# Power_Distribution_-_Strobe_and_Center_B.net
KiCad netlist of a schematic drawn in Altium Designer
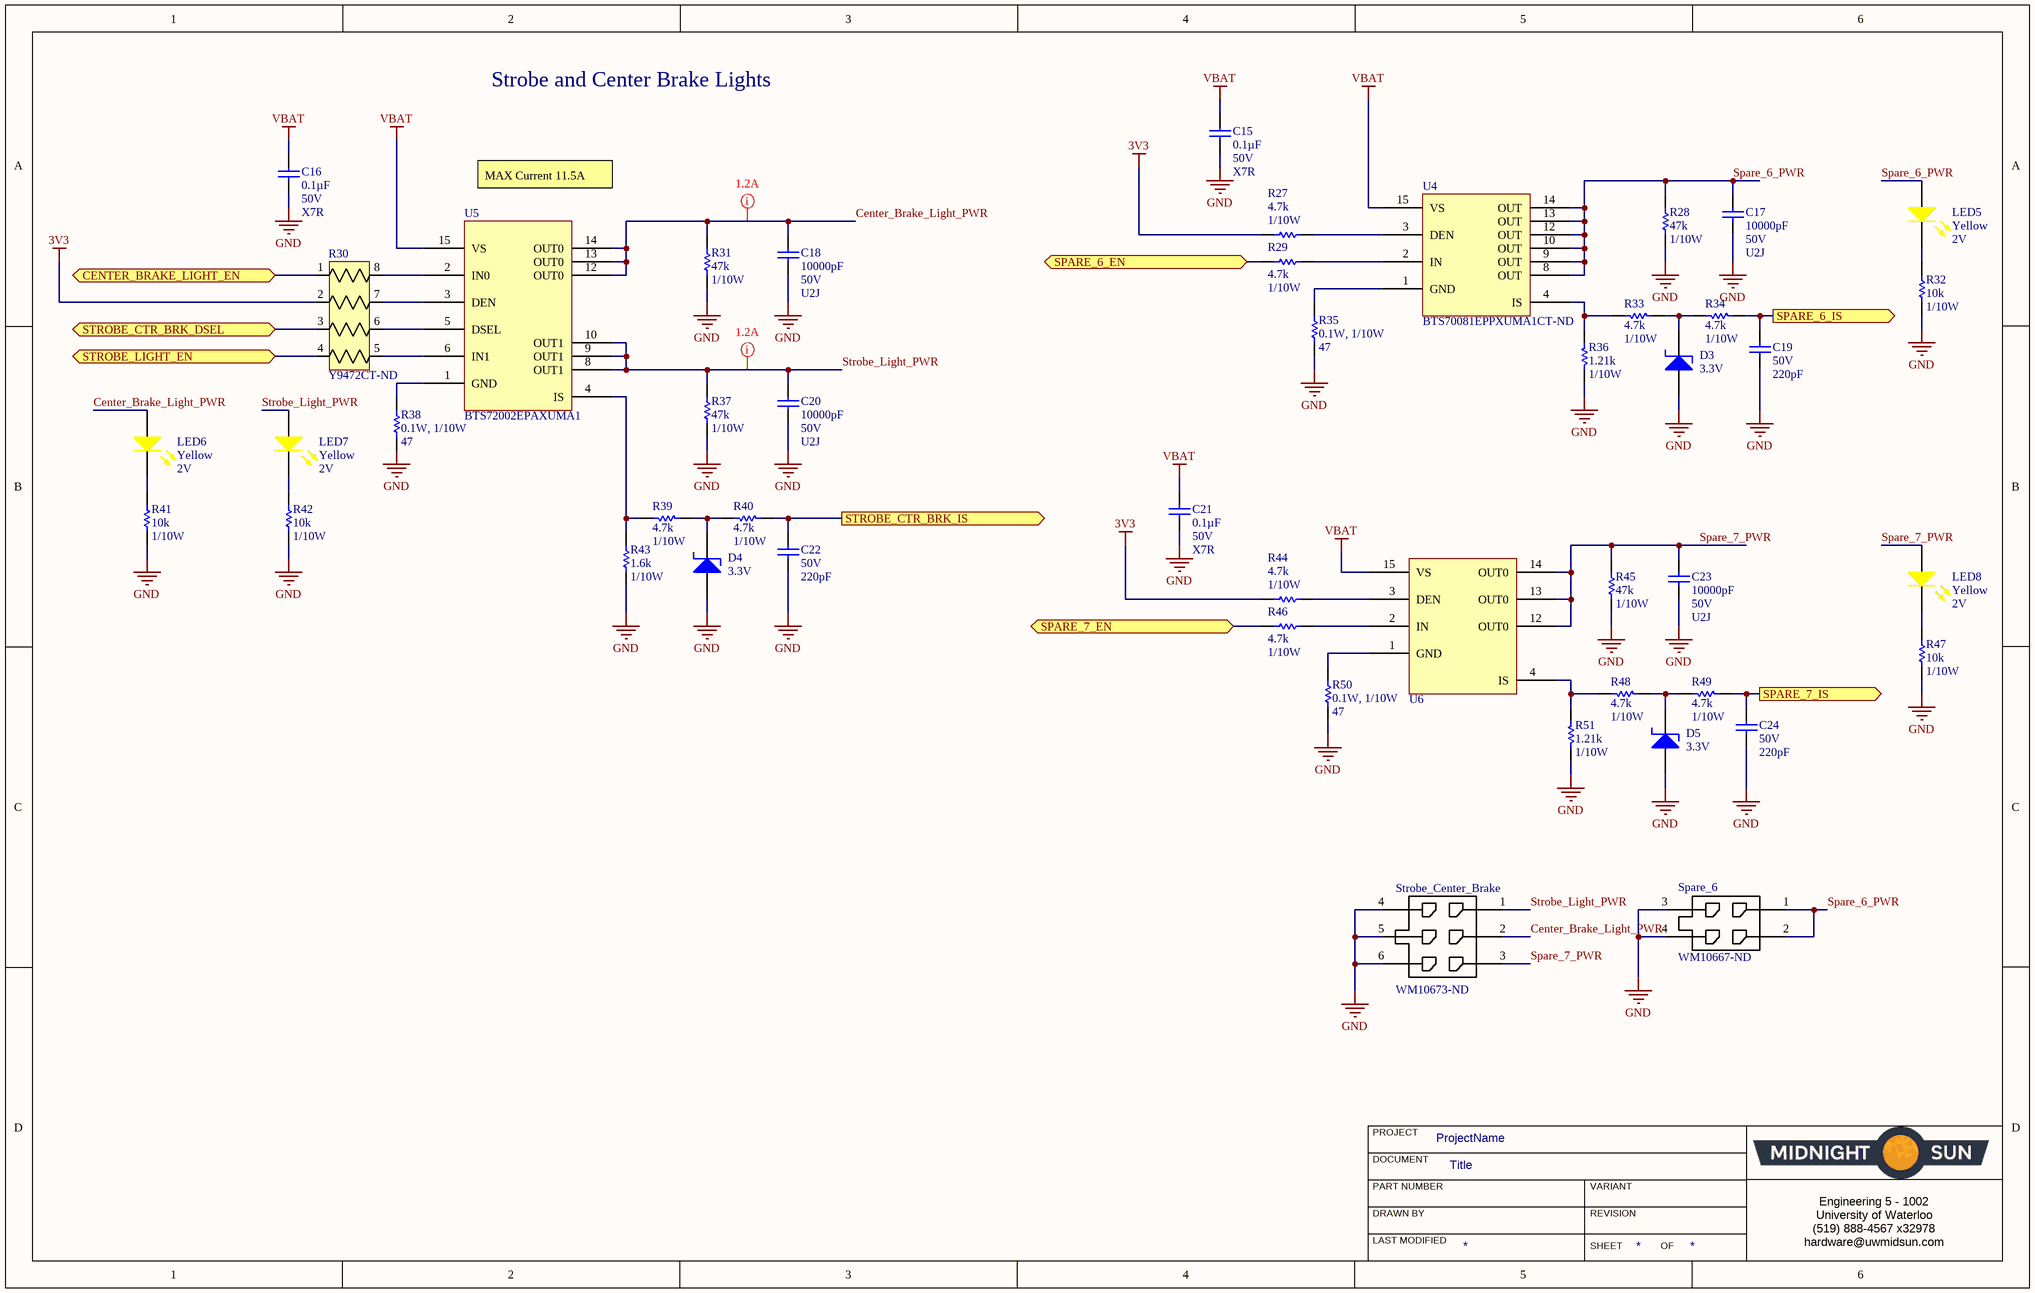
[diagram p0: Power Distribution - Strobe and Center Brake Lights.SchDoc]

(export (version "E")
  (design (tool "Eeschema 10.0.6"))
  (components
    (comp (ref "C15")
      (value "CAP CER 0.1UF 50V 10% X7R 0603")
      (footprint "CAP, 0603")
      (description "0.10µF ±10% 50V Ceramic Capacitor X7R 0603 (1608 Metric)")
      (fields
        (field (name "TOLERANCE") "±10%")
        (field (name "CAPACITANCE") "0.1µF")
        (field (name "VOLTAGE") "50V")
        (field (name "TEMPERATURE COEFFICIENT") "X7R")
      )
      (libsource (lib "Schematic Diagrams") (part "CAP CER 0.1UF 50V 10% X7R 0603"))
    )
    (comp (ref "C16")
      (value "CAP CER 0.1UF 50V 10% X7R 0603")
      (footprint "CAP, 0603")
      (description "0.10µF ±10% 50V Ceramic Capacitor X7R 0603 (1608 Metric)")
      (fields
        (field (name "TOLERANCE") "±10%")
        (field (name "CAPACITANCE") "0.1µF")
        (field (name "VOLTAGE") "50V")
        (field (name "TEMPERATURE COEFFICIENT") "X7R")
      )
      (libsource (lib "Schematic Diagrams") (part "CAP CER 0.1UF 50V 10% X7R 0603"))
    )
    (comp (ref "C17")
      (value "CAP CER 10nF 50V 5% X7R 0603")
      (footprint "CAP, 0603")
      (description "10000pF ±5% 50V Ceramic Capacitor U2J 0603 (1608 Metric)")
      (fields
        (field (name "TOLERANCE") "±5%")
        (field (name "CAPACITANCE") "10000pF")
        (field (name "VOLTAGE") "50V")
        (field (name "TEMPERATURE COEFFICIENT") "U2J")
      )
      (libsource (lib "Schematic Diagrams") (part "CAP CER 10nF 50V 5% X7R 0603"))
    )
    (comp (ref "C18")
      (value "CAP CER 10nF 50V 5% X7R 0603")
      (footprint "CAP, 0603")
      (description "10000pF ±5% 50V Ceramic Capacitor U2J 0603 (1608 Metric)")
      (fields
        (field (name "TOLERANCE") "±5%")
        (field (name "CAPACITANCE") "10000pF")
        (field (name "VOLTAGE") "50V")
        (field (name "TEMPERATURE COEFFICIENT") "U2J")
      )
      (libsource (lib "Schematic Diagrams") (part "CAP CER 10nF 50V 5% X7R 0603"))
    )
    (comp (ref "C19")
      (value "CAP CER 220PF 50V C0G/NP0 0603")
      (footprint "CAP, 0603")
      (description "220pF ±5% 50V Ceramic Capacitor C0G, NP0 0603 (1608 Metric)")
      (fields
        (field (name "MANUFACTURER") "KEMET")
        (field (name "TOLERANCE") "5%")
        (field (name "VOLTAGE RATING") "50V")
        (field (name "CAPACITANCE") "220pF")
      )
      (libsource (lib "Schematic Diagrams") (part "CAP CER 220PF 50V C0G/NP0 0603"))
    )
    (comp (ref "C20")
      (value "CAP CER 10nF 50V 5% X7R 0603")
      (footprint "CAP, 0603")
      (description "10000pF ±5% 50V Ceramic Capacitor U2J 0603 (1608 Metric)")
      (fields
        (field (name "TOLERANCE") "±5%")
        (field (name "CAPACITANCE") "10000pF")
        (field (name "VOLTAGE") "50V")
        (field (name "TEMPERATURE COEFFICIENT") "U2J")
      )
      (libsource (lib "Schematic Diagrams") (part "CAP CER 10nF 50V 5% X7R 0603"))
    )
    (comp (ref "C21")
      (value "CAP CER 0.1UF 50V 10% X7R 0603")
      (footprint "CAP, 0603")
      (description "0.10µF ±10% 50V Ceramic Capacitor X7R 0603 (1608 Metric)")
      (fields
        (field (name "TOLERANCE") "±10%")
        (field (name "CAPACITANCE") "0.1µF")
        (field (name "VOLTAGE") "50V")
        (field (name "TEMPERATURE COEFFICIENT") "X7R")
      )
      (libsource (lib "Schematic Diagrams") (part "CAP CER 0.1UF 50V 10% X7R 0603"))
    )
    (comp (ref "C22")
      (value "CAP CER 220PF 50V C0G/NP0 0603")
      (footprint "CAP, 0603")
      (description "220pF ±5% 50V Ceramic Capacitor C0G, NP0 0603 (1608 Metric)")
      (fields
        (field (name "MANUFACTURER") "KEMET")
        (field (name "TOLERANCE") "5%")
        (field (name "VOLTAGE RATING") "50V")
        (field (name "CAPACITANCE") "220pF")
      )
      (libsource (lib "Schematic Diagrams") (part "CAP CER 220PF 50V C0G/NP0 0603"))
    )
    (comp (ref "C23")
      (value "CAP CER 10nF 50V 5% X7R 0603")
      (footprint "CAP, 0603")
      (description "10000pF ±5% 50V Ceramic Capacitor U2J 0603 (1608 Metric)")
      (fields
        (field (name "TOLERANCE") "±5%")
        (field (name "CAPACITANCE") "10000pF")
        (field (name "VOLTAGE") "50V")
        (field (name "TEMPERATURE COEFFICIENT") "U2J")
      )
      (libsource (lib "Schematic Diagrams") (part "CAP CER 10nF 50V 5% X7R 0603"))
    )
    (comp (ref "C24")
      (value "CAP CER 220PF 50V C0G/NP0 0603")
      (footprint "CAP, 0603")
      (description "220pF ±5% 50V Ceramic Capacitor C0G, NP0 0603 (1608 Metric)")
      (fields
        (field (name "MANUFACTURER") "KEMET")
        (field (name "TOLERANCE") "5%")
        (field (name "VOLTAGE RATING") "50V")
        (field (name "CAPACITANCE") "220pF")
      )
      (libsource (lib "Schematic Diagrams") (part "CAP CER 220PF 50V C0G/NP0 0603"))
    )
    (comp (ref "D3")
      (value "DIODE ZENER 3.3V 200MW SOD323")
      (footprint "sod-323")
      (description "Zener Diode 3.3V 200mW ±5% Surface Mount SOD-323")
      (fields (field (name "VOLTAGE") "3.3V"))
      (libsource (lib "Schematic Diagrams") (part "DIODE ZENER 3.3V 200MW SOD323"))
    )
    (comp (ref "D4")
      (value "DIODE ZENER 3.3V 200MW SOD323")
      (footprint "sod-323")
      (description "Zener Diode 3.3V 200mW ±5% Surface Mount SOD-323")
      (fields (field (name "VOLTAGE") "3.3V"))
      (libsource (lib "Schematic Diagrams") (part "DIODE ZENER 3.3V 200MW SOD323"))
    )
    (comp (ref "D5")
      (value "DIODE ZENER 3.3V 200MW SOD323")
      (footprint "sod-323")
      (description "Zener Diode 3.3V 200mW ±5% Surface Mount SOD-323")
      (fields (field (name "VOLTAGE") "3.3V"))
      (libsource (lib "Schematic Diagrams") (part "DIODE ZENER 3.3V 200MW SOD323"))
    )
    (comp (ref "LED5")
      (value "LED YELLOW CLEAR 2.1V 0603")
      (footprint "LED_0603")
      (description "Yellow 590nm LED Indication - Discrete 2V 0603 (1608 Metric)")
      (fields
        (field (name "MANUFACTURER") "Wurth Electronics Inc.")
        (field (name "MANUFACTURER PART NUMBER") "150060YS75000")
        (field (name "COLOR") "Yellow")
        (field (name "VOLTAGE - FORWARD (VF) (TYP)") "2V")
      )
      (libsource (lib "Schematic Diagrams") (part "LED YELLOW CLEAR 2.1V 0603"))
    )
    (comp (ref "LED6")
      (value "LED YELLOW CLEAR 2.1V 0603")
      (footprint "LED_0603")
      (description "Yellow 590nm LED Indication - Discrete 2V 0603 (1608 Metric)")
      (fields
        (field (name "MANUFACTURER") "Wurth Electronics Inc.")
        (field (name "MANUFACTURER PART NUMBER") "150060YS75000")
        (field (name "COLOR") "Yellow")
        (field (name "VOLTAGE - FORWARD (VF) (TYP)") "2V")
      )
      (libsource (lib "Schematic Diagrams") (part "LED YELLOW CLEAR 2.1V 0603"))
    )
    (comp (ref "LED7")
      (value "LED YELLOW CLEAR 2.1V 0603")
      (footprint "LED_0603")
      (description "Yellow 590nm LED Indication - Discrete 2V 0603 (1608 Metric)")
      (fields
        (field (name "MANUFACTURER") "Wurth Electronics Inc.")
        (field (name "MANUFACTURER PART NUMBER") "150060YS75000")
        (field (name "COLOR") "Yellow")
        (field (name "VOLTAGE - FORWARD (VF) (TYP)") "2V")
      )
      (libsource (lib "Schematic Diagrams") (part "LED YELLOW CLEAR 2.1V 0603"))
    )
    (comp (ref "LED8")
      (value "LED YELLOW CLEAR 2.1V 0603")
      (footprint "LED_0603")
      (description "Yellow 590nm LED Indication - Discrete 2V 0603 (1608 Metric)")
      (fields
        (field (name "MANUFACTURER") "Wurth Electronics Inc.")
        (field (name "MANUFACTURER PART NUMBER") "150060YS75000")
        (field (name "COLOR") "Yellow")
        (field (name "VOLTAGE - FORWARD (VF) (TYP)") "2V")
      )
      (libsource (lib "Schematic Diagrams") (part "LED YELLOW CLEAR 2.1V 0603"))
    )
    (comp (ref "R27")
      (value "RES 4.7K OHM 1% 1/10W 0603")
      (footprint "RES, 0603")
      (description "4.7k Ohm ±1% 0.1W, 1/10W Chip Resistor 0603 (1608 Metric) Moisture Resistant Thick Film")
      (fields
        (field (name "TOLERANCE") "±1%")
        (field (name "RESISTANCE (OHMS)") "4.7k")
        (field (name "POWER (WATTS)") "1/10W")
      )
      (libsource (lib "Schematic Diagrams") (part "RES 4.7K OHM 1% 1/10W 0603"))
    )
    (comp (ref "R28")
      (value "RES 47K OHM 1% 1/10W 0603")
      (footprint "RES, 0603")
      (description "47 kOhms ±1% 0.1W, 1/10W Chip Resistor 0603 (1608 Metric) Automotive AEC-Q200 Thick Film")
      (fields
        (field (name "MANUFACTURER") "Panasonic")
        (field (name "MANUFACTURER PART NUMBER") "ERJ3EKF4702V")
        (field (name "RESISTANCE") "47k")
        (field (name "POWER RATING") "1/10W")
      )
      (libsource (lib "Schematic Diagrams") (part "RES 47K OHM 1% 1/10W 0603"))
    )
    (comp (ref "R29")
      (value "RES 4.7K OHM 1% 1/10W 0603")
      (footprint "RES, 0603")
      (description "4.7k Ohm ±1% 0.1W, 1/10W Chip Resistor 0603 (1608 Metric) Moisture Resistant Thick Film")
      (fields
        (field (name "TOLERANCE") "±1%")
        (field (name "RESISTANCE (OHMS)") "4.7k")
        (field (name "POWER (WATTS)") "1/10W")
      )
      (libsource (lib "Schematic Diagrams") (part "RES 4.7K OHM 1% 1/10W 0603"))
    )
    (comp (ref "R30")
      (value "RES ARRAY 4 RES 4.7K OHM 1206")
      (footprint "RES ARRAY 4RES 1206")
      (fields (field (name "TOLERANCE") "±5%") (field (name "SUPPLIER PART NUMBER 1") "Y9472CT-ND"))
      (libsource (lib "Schematic Diagrams") (part "RES ARRAY 4 RES 4.7K OHM 1206"))
    )
    (comp (ref "R31")
      (value "RES 47K OHM 1% 1/10W 0603")
      (footprint "RES, 0603")
      (description "47 kOhms ±1% 0.1W, 1/10W Chip Resistor 0603 (1608 Metric) Automotive AEC-Q200 Thick Film")
      (fields
        (field (name "MANUFACTURER") "Panasonic")
        (field (name "MANUFACTURER PART NUMBER") "ERJ3EKF4702V")
        (field (name "RESISTANCE") "47k")
        (field (name "POWER RATING") "1/10W")
      )
      (libsource (lib "Schematic Diagrams") (part "RES 47K OHM 1% 1/10W 0603"))
    )
    (comp (ref "R32")
      (value "RES 10K OHM 1% 1/10W 0603")
      (footprint "RES, 0603")
      (description "RES SMD 10K OHM 1% 1/10W 0603")
      (fields
        (field (name "TOLERANCE") "±1%")
        (field (name "RESISTANCE") "10k")
        (field (name "POWER") "1/10W")
      )
      (libsource (lib "Schematic Diagrams") (part "RES 10K OHM 1% 1/10W 0603"))
    )
    (comp (ref "R33")
      (value "RES 4.7K OHM 1% 1/10W 0603")
      (footprint "RES, 0603")
      (description "4.7k Ohm ±1% 0.1W, 1/10W Chip Resistor 0603 (1608 Metric) Moisture Resistant Thick Film")
      (fields
        (field (name "TOLERANCE") "±1%")
        (field (name "RESISTANCE (OHMS)") "4.7k")
        (field (name "POWER (WATTS)") "1/10W")
      )
      (libsource (lib "Schematic Diagrams") (part "RES 4.7K OHM 1% 1/10W 0603"))
    )
    (comp (ref "R34")
      (value "RES 4.7K OHM 1% 1/10W 0603")
      (footprint "RES, 0603")
      (description "4.7k Ohm ±1% 0.1W, 1/10W Chip Resistor 0603 (1608 Metric) Moisture Resistant Thick Film")
      (fields
        (field (name "TOLERANCE") "±1%")
        (field (name "RESISTANCE (OHMS)") "4.7k")
        (field (name "POWER (WATTS)") "1/10W")
      )
      (libsource (lib "Schematic Diagrams") (part "RES 4.7K OHM 1% 1/10W 0603"))
    )
    (comp (ref "R35")
      (value "RES SMD 47 OHM 1% 1/10W 0603")
      (footprint "RES, 0603")
      (fields
        (field (name "TOLERANCE") "±1%")
        (field (name "POWER (WATTS)") "0.1W, 1/10W")
        (field (name "VALUES") "47")
      )
      (libsource (lib "Schematic Diagrams") (part "RES SMD 47 OHM 1% 1/10W 0603"))
    )
    (comp (ref "R36")
      (value "RES 1.21K OHM 1% 1/10W 0603")
      (footprint "RES, 0603")
      (description "1.21k Ohm ±1% 0.1W, 1/10W Chip Resistor 0603 (1608 Metric) Moisture Resistant Thick Film")
      (fields
        (field (name "TOLERANCE") "±1%")
        (field (name "RESISTANCE") "1.21k")
        (field (name "POWER") "1/10W")
      )
      (libsource (lib "Schematic Diagrams") (part "RES 1.21K OHM 1% 1/10W 0603"))
    )
    (comp (ref "R37")
      (value "RES 47K OHM 1% 1/10W 0603")
      (footprint "RES, 0603")
      (description "47 kOhms ±1% 0.1W, 1/10W Chip Resistor 0603 (1608 Metric) Automotive AEC-Q200 Thick Film")
      (fields
        (field (name "MANUFACTURER") "Panasonic")
        (field (name "MANUFACTURER PART NUMBER") "ERJ3EKF4702V")
        (field (name "RESISTANCE") "47k")
        (field (name "POWER RATING") "1/10W")
      )
      (libsource (lib "Schematic Diagrams") (part "RES 47K OHM 1% 1/10W 0603"))
    )
    (comp (ref "R38")
      (value "RES SMD 47 OHM 1% 1/10W 0603")
      (footprint "RES, 0603")
      (fields
        (field (name "TOLERANCE") "±1%")
        (field (name "POWER (WATTS)") "0.1W, 1/10W")
        (field (name "VALUES") "47")
      )
      (libsource (lib "Schematic Diagrams") (part "RES SMD 47 OHM 1% 1/10W 0603"))
    )
    (comp (ref "R39")
      (value "RES 4.7K OHM 1% 1/10W 0603")
      (footprint "RES, 0603")
      (description "4.7k Ohm ±1% 0.1W, 1/10W Chip Resistor 0603 (1608 Metric) Moisture Resistant Thick Film")
      (fields
        (field (name "TOLERANCE") "±1%")
        (field (name "RESISTANCE (OHMS)") "4.7k")
        (field (name "POWER (WATTS)") "1/10W")
      )
      (libsource (lib "Schematic Diagrams") (part "RES 4.7K OHM 1% 1/10W 0603"))
    )
    (comp (ref "R40")
      (value "RES 4.7K OHM 1% 1/10W 0603")
      (footprint "RES, 0603")
      (description "4.7k Ohm ±1% 0.1W, 1/10W Chip Resistor 0603 (1608 Metric) Moisture Resistant Thick Film")
      (fields
        (field (name "TOLERANCE") "±1%")
        (field (name "RESISTANCE (OHMS)") "4.7k")
        (field (name "POWER (WATTS)") "1/10W")
      )
      (libsource (lib "Schematic Diagrams") (part "RES 4.7K OHM 1% 1/10W 0603"))
    )
    (comp (ref "R41")
      (value "RES 10K OHM 1% 1/10W 0603")
      (footprint "RES, 0603")
      (description "RES SMD 10K OHM 1% 1/10W 0603")
      (fields
        (field (name "TOLERANCE") "±1%")
        (field (name "RESISTANCE") "10k")
        (field (name "POWER") "1/10W")
      )
      (libsource (lib "Schematic Diagrams") (part "RES 10K OHM 1% 1/10W 0603"))
    )
    (comp (ref "R42")
      (value "RES 10K OHM 1% 1/10W 0603")
      (footprint "RES, 0603")
      (description "RES SMD 10K OHM 1% 1/10W 0603")
      (fields
        (field (name "TOLERANCE") "±1%")
        (field (name "RESISTANCE") "10k")
        (field (name "POWER") "1/10W")
      )
      (libsource (lib "Schematic Diagrams") (part "RES 10K OHM 1% 1/10W 0603"))
    )
    (comp (ref "R43")
      (value "RES 1.6K OHM 1% 1/10W 0603")
      (footprint "RES, 0603")
      (description "1.6 kOhms ±1% 0.1W, 1/10W Chip Resistor 0603 (1608 Metric) Moisture Resistant Thick Film")
      (fields
        (field (name "MANUFACTURER") "Yageo")
        (field (name "MANUFACTURER PART NUMBER") "RC0603FR-071K6L")
        (field (name "RESISTANCE") "1.6k")
        (field (name "POWER RATING") "1/10W")
      )
      (libsource (lib "Schematic Diagrams") (part "RES 1.6K OHM 1% 1/10W 0603"))
    )
    (comp (ref "R44")
      (value "RES 4.7K OHM 1% 1/10W 0603")
      (footprint "RES, 0603")
      (description "4.7k Ohm ±1% 0.1W, 1/10W Chip Resistor 0603 (1608 Metric) Moisture Resistant Thick Film")
      (fields
        (field (name "TOLERANCE") "±1%")
        (field (name "RESISTANCE (OHMS)") "4.7k")
        (field (name "POWER (WATTS)") "1/10W")
      )
      (libsource (lib "Schematic Diagrams") (part "RES 4.7K OHM 1% 1/10W 0603"))
    )
    (comp (ref "R45")
      (value "RES 47K OHM 1% 1/10W 0603")
      (footprint "RES, 0603")
      (description "47 kOhms ±1% 0.1W, 1/10W Chip Resistor 0603 (1608 Metric) Automotive AEC-Q200 Thick Film")
      (fields
        (field (name "MANUFACTURER") "Panasonic")
        (field (name "MANUFACTURER PART NUMBER") "ERJ3EKF4702V")
        (field (name "RESISTANCE") "47k")
        (field (name "POWER RATING") "1/10W")
      )
      (libsource (lib "Schematic Diagrams") (part "RES 47K OHM 1% 1/10W 0603"))
    )
    (comp (ref "R46")
      (value "RES 4.7K OHM 1% 1/10W 0603")
      (footprint "RES, 0603")
      (description "4.7k Ohm ±1% 0.1W, 1/10W Chip Resistor 0603 (1608 Metric) Moisture Resistant Thick Film")
      (fields
        (field (name "TOLERANCE") "±1%")
        (field (name "RESISTANCE (OHMS)") "4.7k")
        (field (name "POWER (WATTS)") "1/10W")
      )
      (libsource (lib "Schematic Diagrams") (part "RES 4.7K OHM 1% 1/10W 0603"))
    )
    (comp (ref "R47")
      (value "RES 10K OHM 1% 1/10W 0603")
      (footprint "RES, 0603")
      (description "RES SMD 10K OHM 1% 1/10W 0603")
      (fields
        (field (name "TOLERANCE") "±1%")
        (field (name "RESISTANCE") "10k")
        (field (name "POWER") "1/10W")
      )
      (libsource (lib "Schematic Diagrams") (part "RES 10K OHM 1% 1/10W 0603"))
    )
    (comp (ref "R48")
      (value "RES 4.7K OHM 1% 1/10W 0603")
      (footprint "RES, 0603")
      (description "4.7k Ohm ±1% 0.1W, 1/10W Chip Resistor 0603 (1608 Metric) Moisture Resistant Thick Film")
      (fields
        (field (name "TOLERANCE") "±1%")
        (field (name "RESISTANCE (OHMS)") "4.7k")
        (field (name "POWER (WATTS)") "1/10W")
      )
      (libsource (lib "Schematic Diagrams") (part "RES 4.7K OHM 1% 1/10W 0603"))
    )
    (comp (ref "R49")
      (value "RES 4.7K OHM 1% 1/10W 0603")
      (footprint "RES, 0603")
      (description "4.7k Ohm ±1% 0.1W, 1/10W Chip Resistor 0603 (1608 Metric) Moisture Resistant Thick Film")
      (fields
        (field (name "TOLERANCE") "±1%")
        (field (name "RESISTANCE (OHMS)") "4.7k")
        (field (name "POWER (WATTS)") "1/10W")
      )
      (libsource (lib "Schematic Diagrams") (part "RES 4.7K OHM 1% 1/10W 0603"))
    )
    (comp (ref "R50")
      (value "RES SMD 47 OHM 1% 1/10W 0603")
      (footprint "RES, 0603")
      (fields
        (field (name "TOLERANCE") "±1%")
        (field (name "POWER (WATTS)") "0.1W, 1/10W")
        (field (name "VALUES") "47")
      )
      (libsource (lib "Schematic Diagrams") (part "RES SMD 47 OHM 1% 1/10W 0603"))
    )
    (comp (ref "R51")
      (value "RES 1.21K OHM 1% 1/10W 0603")
      (footprint "RES, 0603")
      (description "1.21k Ohm ±1% 0.1W, 1/10W Chip Resistor 0603 (1608 Metric) Moisture Resistant Thick Film")
      (fields
        (field (name "TOLERANCE") "±1%")
        (field (name "RESISTANCE") "1.21k")
        (field (name "POWER") "1/10W")
      )
      (libsource (lib "Schematic Diagrams") (part "RES 1.21K OHM 1% 1/10W 0603"))
    )
    (comp (ref "Spare_6")
      (value "CONN 4POS MICRO-FIT 3mm")
      (footprint "CONN 4POS MICROFIT (2x2)")
      (fields
        (field (name "MANUFACTURER") "Molex, LLC")
        (field (name "MANUFACTURER PART NUMBER") "430450427")
        (field (name "SUPPLIER PART NUMBER 1") "WM10667-ND")
      )
      (libsource (lib "Schematic Diagrams") (part "CONN 4POS MICRO-FIT 3mm"))
    )
    (comp (ref "Strobe_Center_Brake")
      (value "CONN 6POS MICRO-FIT 3mm")
      (footprint "CONN, 6POS MICRO-FIT 3MM")
      (description "Connector Header Through Hole 6 position 0.118\" (3.00mm)")
      (fields (field (name "SUPPLIER PART NUMBER 1") "WM10673-ND"))
      (libsource (lib "Schematic Diagrams") (part "CONN 6POS MICRO-FIT 3mm"))
    )
    (comp (ref "U4")
      (value "IC LOAD SWITCH BTS70081EPPXUMA1")
      (footprint "IC LOAD SWITCH PG-TSDSO-14-22")
      (description "Power Switch/Driver 1:1 N-Channel 11A PG-TSDSO-14-22")
      (fields
        (field (name "MANUFACTURER") "Infineon")
        (field (name "MANUFACTURER PART NUMBER") "BTS70081EPPXUMA1CT-ND")
      )
      (libsource (lib "Schematic Diagrams") (part "IC LOAD SWITCH BTS70081EPPXUMA1"))
    )
    (comp (ref "U5")
      (value "IC LOAD SWITCH BTS7200-2EPA PG-TSDSO-14_1")
      (footprint "IC LOAD SWITCH PG-TSDSO-14-22")
      (description "Power Switch/Driver 1:1 N-Channel 1.2A PG-TSDSO-14-22")
      (fields
        (field (name "MANUFACTURER") "Infineon")
        (field (name "MANUFACTURER PART NUMBER") "BTS72002EPAXUMA1")
      )
      (libsource (lib "Schematic Diagrams") (part "IC LOAD SWITCH BTS7200-2EPA PG-TSDSO-14_1"))
    )
    (comp (ref "U6")
      (value "IC LOAD SWITCH BTS70401EPA PG-TSDSO-14-22")
      (footprint "IC LOAD SWITCH PG-TSDSO-14-22")
      (description "Power Switch/Driver 1:1 N-Channel 4.5A PG-TSDSO-14-22")
      (fields
        (field (name "MANUFACTURER") "Infineon")
        (field (name "MANUFACTURER PART NUMBER") "BTS70401EPAXUMA1")
      )
      (libsource (lib "Schematic Diagrams") (part "IC LOAD SWITCH BTS70401EPA PG-TSDSO-14-22"))
    )
  )
  (nets
    (net (code "1") (name "/CENTER_BRAKE_LIGHT_EN") (class "Default")
      (node (ref "R30") (pin "1") (pinfunction "1_1") (pintype "passive"))
    )
    (net (code "2") (name "/Center_Brake_Light_PWR") (class "Default")
      (node (ref "C18") (pin "1") (pinfunction "1_1") (pintype "passive"))
      (node (ref "LED6") (pin "1") (pinfunction "A_1") (pintype "passive"))
      (node (ref "R31") (pin "1") (pinfunction "1_1") (pintype "passive"))
      (node (ref "Strobe_Center_Brake") (pin "2") (pinfunction "2_2") (pintype "passive"))
      (node (ref "U5") (pin "12") (pinfunction "OUT0_12") (pintype "passive"))
      (node (ref "U5") (pin "13") (pinfunction "OUT0_13") (pintype "passive"))
      (node (ref "U5") (pin "14") (pinfunction "OUT0_14") (pintype "passive"))
    )
    (net (code "3") (name "/SPARE_6_EN") (class "Default")
      (node (ref "R29") (pin "1") (pinfunction "1_1") (pintype "passive"))
    )
    (net (code "4") (name "/SPARE_6_IS") (class "Default")
      (node (ref "C19") (pin "1") (pinfunction "1_1") (pintype "passive"))
      (node (ref "R34") (pin "1") (pinfunction "1_1") (pintype "passive"))
    )
    (net (code "5") (name "/SPARE_7_EN") (class "Default")
      (node (ref "R46") (pin "1") (pinfunction "1_1") (pintype "passive"))
    )
    (net (code "6") (name "/SPARE_7_IS") (class "Default")
      (node (ref "C24") (pin "1") (pinfunction "1_1") (pintype "passive"))
      (node (ref "R49") (pin "1") (pinfunction "1_1") (pintype "passive"))
    )
    (net (code "7") (name "/STROBE_CTR_BRK_DSEL") (class "Default")
      (node (ref "R30") (pin "3") (pinfunction "3_3") (pintype "passive"))
    )
    (net (code "8") (name "/STROBE_CTR_BRK_IS") (class "Default")
      (node (ref "C22") (pin "1") (pinfunction "1_1") (pintype "passive"))
      (node (ref "R40") (pin "1") (pinfunction "1_1") (pintype "passive"))
    )
    (net (code "9") (name "/STROBE_LIGHT_EN") (class "Default")
      (node (ref "R30") (pin "4") (pinfunction "4_4") (pintype "passive"))
    )
    (net (code "10") (name "/Spare_6_PWR") (class "Default")
      (node (ref "C17") (pin "1") (pinfunction "1_1") (pintype "passive"))
      (node (ref "LED5") (pin "1") (pinfunction "A_1") (pintype "passive"))
      (node (ref "R28") (pin "1") (pinfunction "1_1") (pintype "passive"))
      (node (ref "Spare_6") (pin "1") (pinfunction "1_1") (pintype "passive"))
      (node (ref "Spare_6") (pin "2") (pinfunction "2_2") (pintype "passive"))
      (node (ref "U4") (pin "10") (pinfunction "OUT_10") (pintype "passive"))
      (node (ref "U4") (pin "12") (pinfunction "OUT_12") (pintype "passive"))
      (node (ref "U4") (pin "13") (pinfunction "OUT_13") (pintype "passive"))
      (node (ref "U4") (pin "14") (pinfunction "OUT_14") (pintype "passive"))
      (node (ref "U4") (pin "8") (pinfunction "OUT_8") (pintype "passive"))
      (node (ref "U4") (pin "9") (pinfunction "OUT_9") (pintype "passive"))
    )
    (net (code "11") (name "/Spare_7_PWR") (class "Default")
      (node (ref "C23") (pin "1") (pinfunction "1_1") (pintype "passive"))
      (node (ref "LED8") (pin "1") (pinfunction "A_1") (pintype "passive"))
      (node (ref "R45") (pin "1") (pinfunction "1_1") (pintype "passive"))
      (node (ref "Strobe_Center_Brake") (pin "3") (pinfunction "3_3") (pintype "passive"))
      (node (ref "U6") (pin "12") (pinfunction "OUT0_12") (pintype "passive"))
      (node (ref "U6") (pin "13") (pinfunction "OUT0_13") (pintype "passive"))
      (node (ref "U6") (pin "14") (pinfunction "OUT0_14") (pintype "passive"))
    )
    (net (code "12") (name "/Strobe_Light_PWR") (class "Default")
      (node (ref "C20") (pin "1") (pinfunction "1_1") (pintype "passive"))
      (node (ref "LED7") (pin "1") (pinfunction "A_1") (pintype "passive"))
      (node (ref "R37") (pin "1") (pinfunction "1_1") (pintype "passive"))
      (node (ref "Strobe_Center_Brake") (pin "1") (pinfunction "1_1") (pintype "passive"))
      (node (ref "U5") (pin "10") (pinfunction "OUT1_10") (pintype "passive"))
      (node (ref "U5") (pin "8") (pinfunction "OUT1_8") (pintype "passive"))
      (node (ref "U5") (pin "9") (pinfunction "OUT1_9") (pintype "passive"))
    )
    (net (code "13") (name "3V3") (class "Default")
      (node (ref "R27") (pin "1") (pinfunction "1_1") (pintype "passive"))
      (node (ref "R30") (pin "2") (pinfunction "2_2") (pintype "passive"))
      (node (ref "R44") (pin "1") (pinfunction "1_1") (pintype "passive"))
    )
    (net (code "14") (name "GND") (class "Default")
      (node (ref "C15") (pin "2") (pinfunction "2_2") (pintype "passive"))
      (node (ref "C16") (pin "2") (pinfunction "2_2") (pintype "passive"))
      (node (ref "C17") (pin "2") (pinfunction "2_2") (pintype "passive"))
      (node (ref "C18") (pin "2") (pinfunction "2_2") (pintype "passive"))
      (node (ref "C19") (pin "2") (pinfunction "2_2") (pintype "passive"))
      (node (ref "C20") (pin "2") (pinfunction "2_2") (pintype "passive"))
      (node (ref "C21") (pin "2") (pinfunction "2_2") (pintype "passive"))
      (node (ref "C22") (pin "2") (pinfunction "2_2") (pintype "passive"))
      (node (ref "C23") (pin "2") (pinfunction "2_2") (pintype "passive"))
      (node (ref "C24") (pin "2") (pinfunction "2_2") (pintype "passive"))
      (node (ref "D3") (pin "1") (pinfunction "A_1") (pintype "passive"))
      (node (ref "D4") (pin "1") (pinfunction "A_1") (pintype "passive"))
      (node (ref "D5") (pin "1") (pinfunction "A_1") (pintype "passive"))
      (node (ref "R28") (pin "2") (pinfunction "2_2") (pintype "passive"))
      (node (ref "R31") (pin "2") (pinfunction "2_2") (pintype "passive"))
      (node (ref "R32") (pin "2") (pinfunction "2_2") (pintype "passive"))
      (node (ref "R35") (pin "2") (pinfunction "2_2") (pintype "passive"))
      (node (ref "R36") (pin "2") (pinfunction "2_2") (pintype "passive"))
      (node (ref "R37") (pin "2") (pinfunction "2_2") (pintype "passive"))
      (node (ref "R38") (pin "2") (pinfunction "2_2") (pintype "passive"))
      (node (ref "R41") (pin "2") (pinfunction "2_2") (pintype "passive"))
      (node (ref "R42") (pin "2") (pinfunction "2_2") (pintype "passive"))
      (node (ref "R43") (pin "2") (pinfunction "2_2") (pintype "passive"))
      (node (ref "R45") (pin "2") (pinfunction "2_2") (pintype "passive"))
      (node (ref "R47") (pin "2") (pinfunction "2_2") (pintype "passive"))
      (node (ref "R50") (pin "2") (pinfunction "2_2") (pintype "passive"))
      (node (ref "R51") (pin "2") (pinfunction "2_2") (pintype "passive"))
      (node (ref "Spare_6") (pin "3") (pinfunction "3_3") (pintype "passive"))
      (node (ref "Spare_6") (pin "4") (pinfunction "4_4") (pintype "passive"))
      (node (ref "Strobe_Center_Brake") (pin "4") (pinfunction "4_4") (pintype "passive"))
      (node (ref "Strobe_Center_Brake") (pin "5") (pinfunction "5_5") (pintype "passive"))
      (node (ref "Strobe_Center_Brake") (pin "6") (pinfunction "6_6") (pintype "passive"))
    )
    (net (code "15") (name "Net-(D3-K)") (class "Default")
      (node (ref "D3") (pin "2") (pinfunction "K_2") (pintype "passive"))
      (node (ref "R33") (pin "1") (pinfunction "1_1") (pintype "passive"))
      (node (ref "R34") (pin "2") (pinfunction "2_2") (pintype "passive"))
    )
    (net (code "16") (name "Net-(D4-K)") (class "Default")
      (node (ref "D4") (pin "2") (pinfunction "K_2") (pintype "passive"))
      (node (ref "R39") (pin "1") (pinfunction "1_1") (pintype "passive"))
      (node (ref "R40") (pin "2") (pinfunction "2_2") (pintype "passive"))
    )
    (net (code "17") (name "Net-(D5-K)") (class "Default")
      (node (ref "D5") (pin "2") (pinfunction "K_2") (pintype "passive"))
      (node (ref "R48") (pin "1") (pinfunction "1_1") (pintype "passive"))
      (node (ref "R49") (pin "2") (pinfunction "2_2") (pintype "passive"))
    )
    (net (code "18") (name "Net-(LED5-K)") (class "Default")
      (node (ref "LED5") (pin "2") (pinfunction "K_2") (pintype "passive"))
      (node (ref "R32") (pin "1") (pinfunction "1_1") (pintype "passive"))
    )
    (net (code "19") (name "Net-(LED6-K)") (class "Default")
      (node (ref "LED6") (pin "2") (pinfunction "K_2") (pintype "passive"))
      (node (ref "R41") (pin "1") (pinfunction "1_1") (pintype "passive"))
    )
    (net (code "20") (name "Net-(LED7-K)") (class "Default")
      (node (ref "LED7") (pin "2") (pinfunction "K_2") (pintype "passive"))
      (node (ref "R42") (pin "1") (pinfunction "1_1") (pintype "passive"))
    )
    (net (code "21") (name "Net-(LED8-K)") (class "Default")
      (node (ref "LED8") (pin "2") (pinfunction "K_2") (pintype "passive"))
      (node (ref "R47") (pin "1") (pinfunction "1_1") (pintype "passive"))
    )
    (net (code "22") (name "Net-(U4-DEN)") (class "Default")
      (node (ref "R27") (pin "2") (pinfunction "2_2") (pintype "passive"))
      (node (ref "U4") (pin "3") (pinfunction "DEN_3") (pintype "passive"))
    )
    (net (code "23") (name "Net-(U4-GND)") (class "Default")
      (node (ref "R35") (pin "1") (pinfunction "1_1") (pintype "passive"))
      (node (ref "U4") (pin "1") (pinfunction "GND_1") (pintype "passive"))
    )
    (net (code "24") (name "Net-(U4-IN)") (class "Default")
      (node (ref "R29") (pin "2") (pinfunction "2_2") (pintype "passive"))
      (node (ref "U4") (pin "2") (pinfunction "IN_2") (pintype "passive"))
    )
    (net (code "25") (name "Net-(U4-IS)") (class "Default")
      (node (ref "R33") (pin "2") (pinfunction "2_2") (pintype "passive"))
      (node (ref "R36") (pin "1") (pinfunction "1_1") (pintype "passive"))
      (node (ref "U4") (pin "4") (pinfunction "IS_4") (pintype "passive"))
    )
    (net (code "26") (name "Net-(U5-DEN)") (class "Default")
      (node (ref "R30") (pin "7") (pinfunction "7_7") (pintype "passive"))
      (node (ref "U5") (pin "3") (pinfunction "DEN_3") (pintype "passive"))
    )
    (net (code "27") (name "Net-(U5-DSEL)") (class "Default")
      (node (ref "R30") (pin "6") (pinfunction "6_6") (pintype "passive"))
      (node (ref "U5") (pin "5") (pinfunction "DSEL_5") (pintype "passive"))
    )
    (net (code "28") (name "Net-(U5-GND)") (class "Default")
      (node (ref "R38") (pin "1") (pinfunction "1_1") (pintype "passive"))
      (node (ref "U5") (pin "1") (pinfunction "GND_1") (pintype "passive"))
    )
    (net (code "29") (name "Net-(U5-IN0)") (class "Default")
      (node (ref "R30") (pin "8") (pinfunction "8_8") (pintype "passive"))
      (node (ref "U5") (pin "2") (pinfunction "IN0_2") (pintype "passive"))
    )
    (net (code "30") (name "Net-(U5-IN1)") (class "Default")
      (node (ref "R30") (pin "5") (pinfunction "5_5") (pintype "passive"))
      (node (ref "U5") (pin "6") (pinfunction "IN1_6") (pintype "passive"))
    )
    (net (code "31") (name "Net-(U5-IS)") (class "Default")
      (node (ref "R39") (pin "2") (pinfunction "2_2") (pintype "passive"))
      (node (ref "R43") (pin "1") (pinfunction "1_1") (pintype "passive"))
      (node (ref "U5") (pin "4") (pinfunction "IS_4") (pintype "passive"))
    )
    (net (code "32") (name "Net-(U6-DEN)") (class "Default")
      (node (ref "R44") (pin "2") (pinfunction "2_2") (pintype "passive"))
      (node (ref "U6") (pin "3") (pinfunction "DEN_3") (pintype "passive"))
    )
    (net (code "33") (name "Net-(U6-GND)") (class "Default")
      (node (ref "R50") (pin "1") (pinfunction "1_1") (pintype "passive"))
      (node (ref "U6") (pin "1") (pinfunction "GND_1") (pintype "passive"))
    )
    (net (code "34") (name "Net-(U6-IN)") (class "Default")
      (node (ref "R46") (pin "2") (pinfunction "2_2") (pintype "passive"))
      (node (ref "U6") (pin "2") (pinfunction "IN_2") (pintype "passive"))
    )
    (net (code "35") (name "Net-(U6-IS)") (class "Default")
      (node (ref "R48") (pin "2") (pinfunction "2_2") (pintype "passive"))
      (node (ref "R51") (pin "1") (pinfunction "1_1") (pintype "passive"))
      (node (ref "U6") (pin "4") (pinfunction "IS_4") (pintype "passive"))
    )
    (net (code "36") (name "VBAT") (class "Default")
      (node (ref "C15") (pin "1") (pinfunction "1_1") (pintype "passive"))
      (node (ref "C16") (pin "1") (pinfunction "1_1") (pintype "passive"))
      (node (ref "C21") (pin "1") (pinfunction "1_1") (pintype "passive"))
      (node (ref "U4") (pin "15") (pinfunction "VS_15") (pintype "passive"))
      (node (ref "U5") (pin "15") (pinfunction "VS_15") (pintype "passive"))
      (node (ref "U6") (pin "15") (pinfunction "VS_15") (pintype "passive"))
    )
  )
)
